# UBC-Thunderbots_PCB_Power__power-v3_1_pc.net
KiCad netlist of a schematic drawn in Altium Designer
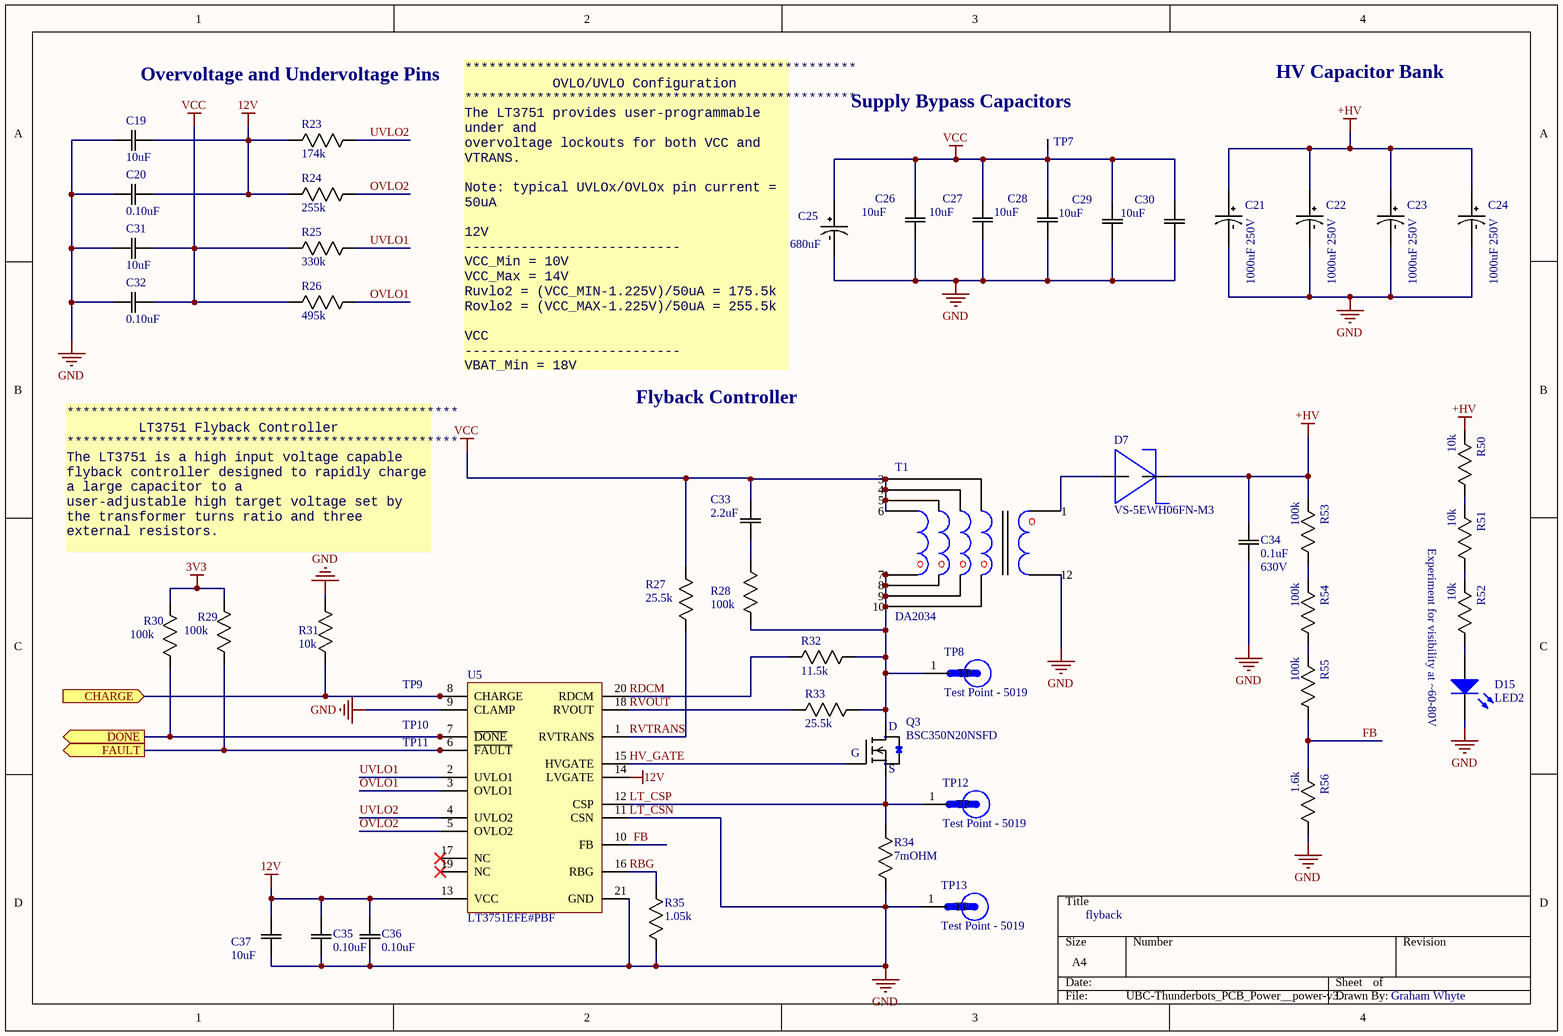
[diagram p0: UBC-Thunderbots_PCB_Power__power-v3.1_pcb__flyback.SchDoc]

(export (version "E")
  (design (tool "Eeschema 10.0.6"))
  (components
    (comp (ref "C19")
      (value "10uF")
      (footprint "0805")
      (description "CAP CER 10UF 35V X7R 0805")
      (fields (field (name "TOLERANCE") "10%"))
      (libsource (lib "") (part "CAP 10uF 35V_1"))
    )
    (comp (ref "C20")
      (value "0.10uF")
      (footprint "0805")
      (description "CAP CER 0.10UF 35V X7R 0603/0805")
      (fields (field (name "TOLERANCE") "10%"))
      (libsource (lib "AltiumLibraries") (part "CAP 0.10uF 35V"))
    )
    (comp (ref "C21")
      (value "1000uF 250V")
      (footprint "RADIAL, CAN - THRU 25.4mm")
      (description "United Chemi-Con\r\nESMQ251VSN102MQ45S")
      (fields
        (field (name "MANUFACTURER") "United Chemi-Con")
        (field (name "MANUFACTURER PART NUMBER") "ESMQ251VSN102MQ45S")
      )
      (libsource (lib "AltiumLibraries") (part "CAP POL 1000uF"))
    )
    (comp (ref "C22")
      (value "1000uF 250V")
      (footprint "RADIAL, CAN - THRU 25.4mm")
      (description "United Chemi-Con\r\nESMQ251VSN102MQ45S")
      (fields
        (field (name "MANUFACTURER") "United Chemi-Con")
        (field (name "MANUFACTURER PART NUMBER") "ESMQ251VSN102MQ45S")
      )
      (libsource (lib "AltiumLibraries") (part "CAP POL 1000uF"))
    )
    (comp (ref "C23")
      (value "1000uF 250V")
      (footprint "RADIAL, CAN - THRU 25.4mm")
      (description "United Chemi-Con\r\nESMQ251VSN102MQ45S")
      (fields
        (field (name "MANUFACTURER") "United Chemi-Con")
        (field (name "MANUFACTURER PART NUMBER") "ESMQ251VSN102MQ45S")
      )
      (libsource (lib "AltiumLibraries") (part "CAP POL 1000uF"))
    )
    (comp (ref "C24")
      (value "1000uF 250V")
      (footprint "RADIAL, CAN - THRU 25.4mm")
      (description "United Chemi-Con\r\nESMQ251VSN102MQ45S")
      (fields
        (field (name "MANUFACTURER") "United Chemi-Con")
        (field (name "MANUFACTURER PART NUMBER") "ESMQ251VSN102MQ45S")
      )
      (libsource (lib "AltiumLibraries") (part "CAP POL 1000uF"))
    )
    (comp (ref "C25")
      (value "680uF")
      (footprint "RADIAL, CAN - THRU 10mm - RIGHTANGLE")
      (description "NICHICON   UHW1V681MPD6 ALUMINUM ELECTROLYTIC CAPACITOR, 680UF, 35V, 20%, RADIAL, FULL REEL")
      (fields (field (name "TOLERANCE") "20%") (field (name "MANUFACTURER") "Nichicon"))
      (libsource (lib "AltiumLibraries") (part "CAP POL 680uF TH"))
    )
    (comp (ref "C26")
      (value "10uF")
      (footprint "1210")
      (description "CAP CER 10UF 35V X7R 0805")
      (fields (field (name "TOLERANCE") "10%"))
      (libsource (lib "AltiumLibraries") (part "CAP 10uF 35V"))
    )
    (comp (ref "C27")
      (value "10uF")
      (footprint "1210")
      (description "CAP CER 10UF 35V X7R 0805")
      (fields (field (name "TOLERANCE") "10%"))
      (libsource (lib "") (part "CAP 10uF 35V_1"))
    )
    (comp (ref "C28")
      (value "10uF")
      (footprint "1210")
      (description "CAP CER 10UF 35V X7R 0805")
      (fields (field (name "TOLERANCE") "10%"))
      (libsource (lib "") (part "CAP 10uF 35V_1"))
    )
    (comp (ref "C29")
      (value "10uF")
      (footprint "1210")
      (description "CAP CER 10UF 35V X7R 0805")
      (fields (field (name "TOLERANCE") "10%"))
      (libsource (lib "") (part "CAP 10uF 35V_1"))
    )
    (comp (ref "C30")
      (value "10uF")
      (footprint "1210")
      (description "CAP CER 10UF 35V X7R 0805")
      (fields (field (name "TOLERANCE") "10%"))
      (libsource (lib "") (part "CAP 10uF 35V_1"))
    )
    (comp (ref "C31")
      (value "10uF")
      (footprint "0805")
      (description "CAP CER 10UF 35V X7R 0805")
      (fields (field (name "TOLERANCE") "10%"))
      (libsource (lib "") (part "CAP 10uF 35V_1"))
    )
    (comp (ref "C32")
      (value "0.10uF")
      (footprint "0805")
      (description "CAP CER 0.10UF 35V X7R 0603/0805")
      (fields (field (name "TOLERANCE") "10%"))
      (libsource (lib "AltiumLibraries") (part "CAP 0.10uF 35V"))
    )
    (comp (ref "C33")
      (value "2.2uF")
      (footprint "0805")
      (description "CAP CER 2.2UF 16V X5R 0603/0805")
      (fields (field (name "TOLERANCE") "10%"))
      (libsource (lib "AltiumLibraries") (part "CAP 2.2uF 16V"))
    )
    (comp (ref "C34")
      (value "0.1uF")
      (footprint "1210")
      (description "CAP CER 0.1uF 630V X7R 1210")
      (fields (field (name "TOLERANCE") "10%") (field (name "RATING") "630V"))
      (libsource (lib "AltiumLibraries") (part "CAP 0.1uF 630V"))
    )
    (comp (ref "C35")
      (value "0.10uF")
      (footprint "0805")
      (description "CAP CER 0.10UF 35V X7R 0603/0805")
      (fields (field (name "TOLERANCE") "10%"))
      (libsource (lib "AltiumLibraries") (part "CAP 0.10uF 35V"))
    )
    (comp (ref "C36")
      (value "0.10uF")
      (footprint "0805")
      (description "CAP CER 0.10UF 35V X7R 0603/0805")
      (fields (field (name "TOLERANCE") "10%"))
      (libsource (lib "AltiumLibraries") (part "CAP 0.10uF 35V"))
    )
    (comp (ref "C37")
      (value "10uF")
      (footprint "0805")
      (description "CAP CER 10UF 35V X7R 0805")
      (fields (field (name "TOLERANCE") "10%"))
      (libsource (lib "") (part "CAP 10uF 35V_1"))
    )
    (comp (ref "D7")
      (value "VS-5EWH06FN-M3")
      (footprint "DPAK (TO-252)")
      (description "Diode Switching 600V 5A DPAK")
      (fields (field (name "MF") "Vishay Diodes"))
      (libsource (lib "AltiumLibraries") (part "VS-5EWH06FN-M3"))
    )
    (comp (ref "D15")
      (value "LED2")
      (footprint "3.2X1.6X1.1")
      (description "Typical RED, GREEN, YELLOW, AMBER GaAs LED")
      (libsource (lib "AltiumLibraries") (part "LED GREEN SMD"))
    )
    (comp (ref "Q3")
      (value "BSC350N20NSFD")
      (footprint "8-PowerSMD")
      (description "MOSFET N-CH 36A 200V")
      (fields (field (name "MF") "Infineon"))
      (libsource (lib "AltiumLibraries") (part "MOSFET BSC320N20NS3"))
    )
    (comp (ref "R23")
      (value "174k")
      (footprint "0805")
      (description "RES SMD 174K OHM 1% 1/8W 0805")
      (fields
        (field (name "MANUFACTURER") "Yageo")
        (field (name "MANUFACTURER PART NUMBER") "RC0805FR-07174KL")
      )
      (libsource (lib "AltiumLibraries") (part "RES 174k 1/8W"))
    )
    (comp (ref "R24")
      (value "255k")
      (footprint "0805")
      (description "0805 Resistor, 6A, 0.125W, 25ppm, 0.1%, 255K")
      (fields
        (field (name "MANUFACTURER") "Panasonic")
        (field (name "MANUFACTURER PART NUMBER") "ERA-6AEB2553V")
      )
      (libsource (lib "AltiumLibraries") (part "RES 255k 0805"))
    )
    (comp (ref "R25")
      (value "330k")
      (footprint "0805")
      (description "RES SMD 274K OHM 1% 1/8W 0805")
      (libsource (lib "AltiumLibraries") (part "RES 330k 1/8W - 1%"))
    )
    (comp (ref "R26")
      (value "495k")
      (footprint "0805")
      (description "RES SMD 499K OHM 1% 1/8W 0805")
      (fields
        (field (name "MANUFACTURER") "Yageo")
        (field (name "MANUFACTURER PART NUMBER") "RC0805FR-07499KL")
      )
      (libsource (lib "AltiumLibraries") (part "RES 495k 1/8W"))
    )
    (comp (ref "R27")
      (value "25.5k")
      (footprint "0805")
      (description "RES SMD 25.5K OHM 0.1% 1/8W 0805")
      (fields
        (field (name "MANUFACTURER") "Panasonic")
        (field (name "MANUFACTURER PART NUMBER") "ERA-6AEB2552V")
      )
      (libsource (lib "AltiumLibraries") (part "RES 25.5k 1/8W"))
    )
    (comp (ref "R28")
      (value "100k")
      (footprint "0805")
      (description "RES SMD 100K OHM 1% 1/8W 0805")
      (fields (field (name "TOLERANCE") "1%"))
      (libsource (lib "") (part "RES 100k 1/8W - 1%_1"))
    )
    (comp (ref "R29")
      (value "100k")
      (footprint "0805")
      (description "RES SMD 100K OHM 1% 1/8W 0805")
      (fields (field (name "TOLERANCE") "1%"))
      (libsource (lib "AltiumLibraries") (part "RES 100k 1/8W - 1%"))
    )
    (comp (ref "R30")
      (value "100k")
      (footprint "0805")
      (description "RES SMD 100K OHM 1% 1/8W 0805")
      (fields (field (name "TOLERANCE") "1%"))
      (libsource (lib "AltiumLibraries") (part "RES 100k 1/8W - 1%"))
    )
    (comp (ref "R31")
      (value "10k")
      (footprint "0805")
      (description "RES SMD 10K OHM 1% 1/8W 0805")
      (fields (field (name "TOLERANCE") "1%"))
      (libsource (lib "AltiumLibraries") (part "RES 10k 1/8W - 1%"))
    )
    (comp (ref "R32")
      (value "11.5k")
      (footprint "0805")
      (description "RES SMD 11.5K OHM 0.1% 1/8W 0805 Thin Film")
      (fields
        (field (name "MANUFACTURER") "Panasonic")
        (field (name "MANUFACTURER PART NUMBER") "ERA-6AEB1152V")
      )
      (libsource (lib "AltiumLibraries") (part "RES 11.5k 1/8W"))
    )
    (comp (ref "R33")
      (value "25.5k")
      (footprint "0805")
      (description "RES SMD 25.5K OHM 0.1% 1/8W 0805")
      (fields
        (field (name "MANUFACTURER") "Panasonic")
        (field (name "MANUFACTURER PART NUMBER") "ERA-6AEB2552V")
      )
      (libsource (lib "") (part "RES 25.5k 1/8W_1"))
    )
    (comp (ref "R34")
      (value "7mOHM")
      (footprint "2512")
      (description "RES SMD 7m OHM 1% 3W 2512")
      (fields (field (name "TOLERANCE") "1%") (field (name "MFG") "VISHAY"))
      (libsource (lib "AltiumLibraries") (part "RES 7m 3W"))
    )
    (comp (ref "R35")
      (value "1.05k")
      (footprint "0805")
      (description "RES SMD 1.05K OHM 0.1% 1/8W 0805")
      (fields (field (name "TOLERANCE") "0.1%"))
      (libsource (lib "AltiumLibraries") (part "RES 1.05k 1/8W"))
    )
    (comp (ref "R50")
      (value "10k")
      (footprint "1206")
      (description "RES SMD 10K OHM 1% 1W 1206")
      (fields (field (name "TOLERANCE") "1%"))
      (libsource (lib "AltiumLibraries") (part "RES 10k 1W"))
    )
    (comp (ref "R51")
      (value "10k")
      (footprint "1206")
      (description "RES SMD 10K OHM 1% 1W 1206")
      (fields (field (name "TOLERANCE") "1%"))
      (libsource (lib "") (part "RES 10k 1W_1"))
    )
    (comp (ref "R52")
      (value "10k")
      (footprint "1206")
      (description "RES SMD 10K OHM 1% 1W 1206")
      (fields (field (name "TOLERANCE") "1%"))
      (libsource (lib "AltiumLibraries") (part "RES 10k 1W"))
    )
    (comp (ref "R53")
      (value "100k")
      (footprint "0805")
      (description "RES SMD 100K OHM 1% 1/8W 0805")
      (fields (field (name "TOLERANCE") "1%"))
      (libsource (lib "AltiumLibraries") (part "RES 100k 1/8W - 1%"))
    )
    (comp (ref "R54")
      (value "100k")
      (footprint "0805")
      (description "RES SMD 100K OHM 1% 1/8W 0805")
      (fields (field (name "TOLERANCE") "1%"))
      (libsource (lib "") (part "RES 100k 1/8W - 1%_1"))
    )
    (comp (ref "R55")
      (value "100k")
      (footprint "0805")
      (description "RES SMD 100K OHM 1% 1/8W 0805")
      (fields (field (name "TOLERANCE") "1%"))
      (libsource (lib "AltiumLibraries") (part "RES 100k 1/8W - 1%"))
    )
    (comp (ref "R56")
      (value "1.6k")
      (footprint "0805")
      (description "RES SMD 1.6K OHM 5% 1/8W 0805")
      (fields (field (name "TOLERANCE") "5%"))
      (libsource (lib "AltiumLibraries") (part "RES 1.6k 1/8W"))
    )
    (comp (ref "T1")
      (value "DA2034")
      (footprint "DA2034")
      (description "Audio Transformers / Signal Transformers DA2032 Cap Chrgr For Linear LT3750/51")
      (libsource (lib "AltiumLibraries") (part "DA2034"))
    )
    (comp (ref "TP7")
      (value "Test Point (Via)")
      (footprint "TP")
      (libsource (lib "AltiumLibraries") (part "Test Point (Via)"))
    )
    (comp (ref "TP8")
      (value "Test Point - 5019")
      (footprint "TP380X203")
      (description "PC Test Point, Miniature Phosphor Bronze, Silver Plating Surface Mount Mounting Type")
      (fields (field (name "MP") "5019") (field (name "MF") "Keystone Electronics"))
      (libsource (lib "AltiumLibraries") (part "Test Point - 5019"))
    )
    (comp (ref "TP9")
      (value "Test Point (Via)")
      (footprint "TP")
      (libsource (lib "AltiumLibraries") (part "Test Point (Via)"))
    )
    (comp (ref "TP10")
      (value "Test Point (Via)")
      (footprint "TP")
      (libsource (lib "AltiumLibraries") (part "Test Point (Via)"))
    )
    (comp (ref "TP11")
      (value "Test Point (Via)")
      (footprint "TP")
      (libsource (lib "AltiumLibraries") (part "Test Point (Via)"))
    )
    (comp (ref "TP12")
      (value "Test Point - 5019")
      (footprint "TP380X203")
      (description "PC Test Point, Miniature Phosphor Bronze, Silver Plating Surface Mount Mounting Type")
      (fields (field (name "MP") "5019") (field (name "MF") "Keystone Electronics"))
      (libsource (lib "AltiumLibraries") (part "Test Point - 5019"))
    )
    (comp (ref "TP13")
      (value "Test Point - 5019")
      (footprint "TP380X203")
      (description "PC Test Point, Miniature Phosphor Bronze, Silver Plating Surface Mount Mounting Type")
      (fields (field (name "MP") "5019") (field (name "MF") "Keystone Electronics"))
      (libsource (lib "AltiumLibraries") (part "Test Point - 5019"))
    )
    (comp (ref "U5")
      (value "LT3751EFE#PBF")
      (footprint "LT-FE-20-EPV-CB_L")
      (description "Controller to 20-Pin TSSOP EP")
      (fields (field (name "MANUFACTURER") "Analog Devices / Linear Technology"))
      (libsource (lib "AltiumLibraries") (part "LT3751EFE#PBF"))
    )
  )
  (nets
    (net (code "1") (name "+HV") (class "Default")
      (node (ref "C21") (pin "POS") (pinfunction "POS_POS") (pintype "passive"))
      (node (ref "C22") (pin "POS") (pinfunction "POS_POS") (pintype "passive"))
      (node (ref "C23") (pin "POS") (pinfunction "POS_POS") (pintype "passive"))
      (node (ref "C24") (pin "POS") (pinfunction "POS_POS") (pintype "passive"))
      (node (ref "C34") (pin "1") (pinfunction "C1_1") (pintype "passive"))
      (node (ref "D7") (pin "OUT") (pinfunction "OUT_OUT") (pintype "passive"))
      (node (ref "R50") (pin "2") (pinfunction "R2_2") (pintype "passive"))
      (node (ref "R53") (pin "2") (pinfunction "R2_2") (pintype "passive"))
    )
    (net (code "2") (name "/CHARGE") (class "Default")
      (node (ref "R31") (pin "2") (pinfunction "R2_2") (pintype "passive"))
      (node (ref "TP9") (pin "1") (pinfunction "1_1") (pintype "passive"))
      (node (ref "U5") (pin "8") (pinfunction "CHARGE_8") (pintype "passive"))
    )
    (net (code "3") (name "/DONE") (class "Default")
      (node (ref "R30") (pin "1") (pinfunction "R1_1") (pintype "passive"))
      (node (ref "TP10") (pin "1") (pinfunction "1_1") (pintype "passive"))
      (node (ref "U5") (pin "7") (pinfunction "~{DONE}_7") (pintype "passive"))
    )
    (net (code "4") (name "/FAULT") (class "Default")
      (node (ref "R29") (pin "1") (pinfunction "R1_1") (pintype "passive"))
      (node (ref "TP11") (pin "1") (pinfunction "1_1") (pintype "passive"))
      (node (ref "U5") (pin "6") (pinfunction "~{FAULT}_6") (pintype "passive"))
    )
    (net (code "5") (name "/FB") (class "Default")
      (node (ref "R55") (pin "1") (pinfunction "R1_1") (pintype "passive"))
      (node (ref "R56") (pin "2") (pinfunction "R2_2") (pintype "passive"))
      (node (ref "U5") (pin "10") (pinfunction "FB_10") (pintype "passive"))
    )
    (net (code "6") (name "/HV_GATE") (class "Default")
      (node (ref "Q3") (pin "G") (pinfunction "G_G") (pintype "passive"))
      (node (ref "U5") (pin "15") (pinfunction "HVGATE_15") (pintype "passive"))
    )
    (net (code "7") (name "/LT_CSP") (class "Default")
      (node (ref "Q3") (pin "S") (pinfunction "S_S") (pintype "passive"))
      (node (ref "R34") (pin "2") (pinfunction "R2_2") (pintype "passive"))
      (node (ref "TP12") (pin "1") (pinfunction "TP_1") (pintype "passive"))
      (node (ref "U5") (pin "12") (pinfunction "CSP_12") (pintype "passive"))
    )
    (net (code "8") (name "/OVLO1") (class "Default")
      (node (ref "R26") (pin "1") (pinfunction "R1_1") (pintype "passive"))
      (node (ref "U5") (pin "3") (pinfunction "OVLO1_3") (pintype "passive"))
    )
    (net (code "9") (name "/OVLO2") (class "Default")
      (node (ref "R24") (pin "1") (pinfunction "R1_1") (pintype "passive"))
      (node (ref "U5") (pin "5") (pinfunction "OVLO2_5") (pintype "passive"))
    )
    (net (code "10") (name "/RBG") (class "Default")
      (node (ref "R35") (pin "1") (pinfunction "R1_1") (pintype "passive"))
      (node (ref "U5") (pin "16") (pinfunction "RBG_16") (pintype "passive"))
    )
    (net (code "11") (name "/RDCM") (class "Default")
      (node (ref "R32") (pin "2") (pinfunction "R2_2") (pintype "passive"))
      (node (ref "U5") (pin "20") (pinfunction "RDCM_20") (pintype "passive"))
    )
    (net (code "12") (name "/RVOUT") (class "Default")
      (node (ref "R33") (pin "2") (pinfunction "R2_2") (pintype "passive"))
      (node (ref "U5") (pin "18") (pinfunction "RVOUT_18") (pintype "passive"))
    )
    (net (code "13") (name "/RVTRANS") (class "Default")
      (node (ref "R27") (pin "2") (pinfunction "R2_2") (pintype "passive"))
      (node (ref "U5") (pin "1") (pinfunction "RVTRANS_1") (pintype "passive"))
    )
    (net (code "14") (name "/UVLO1") (class "Default")
      (node (ref "R25") (pin "1") (pinfunction "R1_1") (pintype "passive"))
      (node (ref "U5") (pin "2") (pinfunction "UVLO1_2") (pintype "passive"))
    )
    (net (code "15") (name "/UVLO2") (class "Default")
      (node (ref "R23") (pin "1") (pinfunction "R1_1") (pintype "passive"))
      (node (ref "U5") (pin "4") (pinfunction "UVLO2_4") (pintype "passive"))
    )
    (net (code "16") (name "3V3") (class "Default")
      (node (ref "R29") (pin "2") (pinfunction "R2_2") (pintype "passive"))
      (node (ref "R30") (pin "2") (pinfunction "R2_2") (pintype "passive"))
    )
    (net (code "17") (name "12V") (class "Default")
      (node (ref "C19") (pin "2") (pinfunction "C2_2") (pintype "passive"))
      (node (ref "C20") (pin "2") (pinfunction "C2_2") (pintype "passive"))
      (node (ref "C35") (pin "1") (pinfunction "C1_1") (pintype "passive"))
      (node (ref "C36") (pin "1") (pinfunction "C1_1") (pintype "passive"))
      (node (ref "C37") (pin "1") (pinfunction "C1_1") (pintype "passive"))
      (node (ref "R23") (pin "2") (pinfunction "R2_2") (pintype "passive"))
      (node (ref "R24") (pin "2") (pinfunction "R2_2") (pintype "passive"))
      (node (ref "U5") (pin "13") (pinfunction "VCC_13") (pintype "passive"))
      (node (ref "U5") (pin "14") (pinfunction "LVGATE_14") (pintype "passive"))
    )
    (net (code "18") (name "GND") (class "Default")
      (node (ref "C19") (pin "1") (pinfunction "C1_1") (pintype "passive"))
      (node (ref "C20") (pin "1") (pinfunction "C1_1") (pintype "passive"))
      (node (ref "C21") (pin "NEG") (pinfunction "NEG_NEG") (pintype "passive"))
      (node (ref "C22") (pin "NEG") (pinfunction "NEG_NEG") (pintype "passive"))
      (node (ref "C23") (pin "NEG") (pinfunction "NEG_NEG") (pintype "passive"))
      (node (ref "C24") (pin "NEG") (pinfunction "NEG_NEG") (pintype "passive"))
      (node (ref "C25") (pin "NEG") (pinfunction "NEG_NEG") (pintype "passive"))
      (node (ref "C26") (pin "1") (pinfunction "C1_1") (pintype "passive"))
      (node (ref "C27") (pin "1") (pinfunction "C1_1") (pintype "passive"))
      (node (ref "C28") (pin "1") (pinfunction "C1_1") (pintype "passive"))
      (node (ref "C29") (pin "1") (pinfunction "C1_1") (pintype "passive"))
      (node (ref "C30") (pin "1") (pinfunction "C1_1") (pintype "passive"))
      (node (ref "C31") (pin "1") (pinfunction "C1_1") (pintype "passive"))
      (node (ref "C32") (pin "1") (pinfunction "C1_1") (pintype "passive"))
      (node (ref "C34") (pin "2") (pinfunction "C2_2") (pintype "passive"))
      (node (ref "C35") (pin "2") (pinfunction "C2_2") (pintype "passive"))
      (node (ref "C36") (pin "2") (pinfunction "C2_2") (pintype "passive"))
      (node (ref "C37") (pin "2") (pinfunction "C2_2") (pintype "passive"))
      (node (ref "D15") (pin "2") (pinfunction "K_2") (pintype "passive"))
      (node (ref "R31") (pin "1") (pinfunction "R1_1") (pintype "passive"))
      (node (ref "R34") (pin "1") (pinfunction "R1_1") (pintype "passive"))
      (node (ref "R35") (pin "2") (pinfunction "R2_2") (pintype "passive"))
      (node (ref "R56") (pin "1") (pinfunction "R1_1") (pintype "passive"))
      (node (ref "T1") (pin "12") (pinfunction "12_12") (pintype "passive"))
      (node (ref "TP13") (pin "1") (pinfunction "TP_1") (pintype "passive"))
      (node (ref "U5") (pin "11") (pinfunction "CSN_11") (pintype "passive"))
      (node (ref "U5") (pin "21") (pinfunction "GND_21") (pintype "passive"))
      (node (ref "U5") (pin "9") (pinfunction "CLAMP_9") (pintype "passive"))
    )
    (net (code "19") (name "Net-(C33-C1)") (class "Default")
      (node (ref "C33") (pin "1") (pinfunction "C1_1") (pintype "passive"))
      (node (ref "R28") (pin "1") (pinfunction "R1_1") (pintype "passive"))
    )
    (net (code "20") (name "Net-(D7-PadIN)") (class "Default")
      (node (ref "D7") (pin "IN") (pinfunction "IN_IN") (pintype "passive"))
      (node (ref "T1") (pin "1") (pinfunction "1_1") (pintype "passive"))
    )
    (net (code "21") (name "Net-(D15-A)") (class "Default")
      (node (ref "D15") (pin "1") (pinfunction "A_1") (pintype "passive"))
      (node (ref "R52") (pin "1") (pinfunction "R1_1") (pintype "passive"))
    )
    (net (code "22") (name "Net-(R28-R2)") (class "Default")
      (node (ref "Q3") (pin "D") (pinfunction "D_D") (pintype "passive"))
      (node (ref "R28") (pin "2") (pinfunction "R2_2") (pintype "passive"))
      (node (ref "R32") (pin "1") (pinfunction "R1_1") (pintype "passive"))
      (node (ref "R33") (pin "1") (pinfunction "R1_1") (pintype "passive"))
      (node (ref "T1") (pin "10") (pinfunction "10_10") (pintype "passive"))
      (node (ref "T1") (pin "7") (pinfunction "7_7") (pintype "passive"))
      (node (ref "T1") (pin "8") (pinfunction "8_8") (pintype "passive"))
      (node (ref "T1") (pin "9") (pinfunction "9_9") (pintype "passive"))
      (node (ref "TP8") (pin "1") (pinfunction "TP_1") (pintype "passive"))
    )
    (net (code "23") (name "Net-(R50-R1)") (class "Default")
      (node (ref "R50") (pin "1") (pinfunction "R1_1") (pintype "passive"))
      (node (ref "R51") (pin "2") (pinfunction "R2_2") (pintype "passive"))
    )
    (net (code "24") (name "Net-(R51-R1)") (class "Default")
      (node (ref "R51") (pin "1") (pinfunction "R1_1") (pintype "passive"))
      (node (ref "R52") (pin "2") (pinfunction "R2_2") (pintype "passive"))
    )
    (net (code "25") (name "Net-(R53-R1)") (class "Default")
      (node (ref "R53") (pin "1") (pinfunction "R1_1") (pintype "passive"))
      (node (ref "R54") (pin "2") (pinfunction "R2_2") (pintype "passive"))
    )
    (net (code "26") (name "Net-(R54-R1)") (class "Default")
      (node (ref "R54") (pin "1") (pinfunction "R1_1") (pintype "passive"))
      (node (ref "R55") (pin "2") (pinfunction "R2_2") (pintype "passive"))
    )
    (net (code "27") (name "VCC") (class "Default")
      (node (ref "C25") (pin "POS") (pinfunction "POS_POS") (pintype "passive"))
      (node (ref "C26") (pin "2") (pinfunction "C2_2") (pintype "passive"))
      (node (ref "C27") (pin "2") (pinfunction "C2_2") (pintype "passive"))
      (node (ref "C28") (pin "2") (pinfunction "C2_2") (pintype "passive"))
      (node (ref "C29") (pin "2") (pinfunction "C2_2") (pintype "passive"))
      (node (ref "C30") (pin "2") (pinfunction "C2_2") (pintype "passive"))
      (node (ref "C31") (pin "2") (pinfunction "C2_2") (pintype "passive"))
      (node (ref "C32") (pin "2") (pinfunction "C2_2") (pintype "passive"))
      (node (ref "C33") (pin "2") (pinfunction "C2_2") (pintype "passive"))
      (node (ref "R25") (pin "2") (pinfunction "R2_2") (pintype "passive"))
      (node (ref "R26") (pin "2") (pinfunction "R2_2") (pintype "passive"))
      (node (ref "R27") (pin "1") (pinfunction "R1_1") (pintype "passive"))
      (node (ref "T1") (pin "3") (pinfunction "3_3") (pintype "passive"))
      (node (ref "T1") (pin "4") (pinfunction "4_4") (pintype "passive"))
      (node (ref "T1") (pin "5") (pinfunction "5_5") (pintype "passive"))
      (node (ref "T1") (pin "6") (pinfunction "6_6") (pintype "passive"))
      (node (ref "TP7") (pin "1") (pinfunction "1_1") (pintype "passive"))
    )
    (net (code "28") (name "unconnected-(U5-NC-Pad17)") (class "Default")
      (node (ref "U5") (pin "17") (pinfunction "NC_17") (pintype "passive+no_connect"))
    )
    (net (code "29") (name "unconnected-(U5-NC-Pad19)") (class "Default")
      (node (ref "U5") (pin "19") (pinfunction "NC_19") (pintype "passive+no_connect"))
    )
  )
)
